# Adafruit_CAN_Bus_BFF.net
KiCad netlist of a schematic drawn in EAGLE
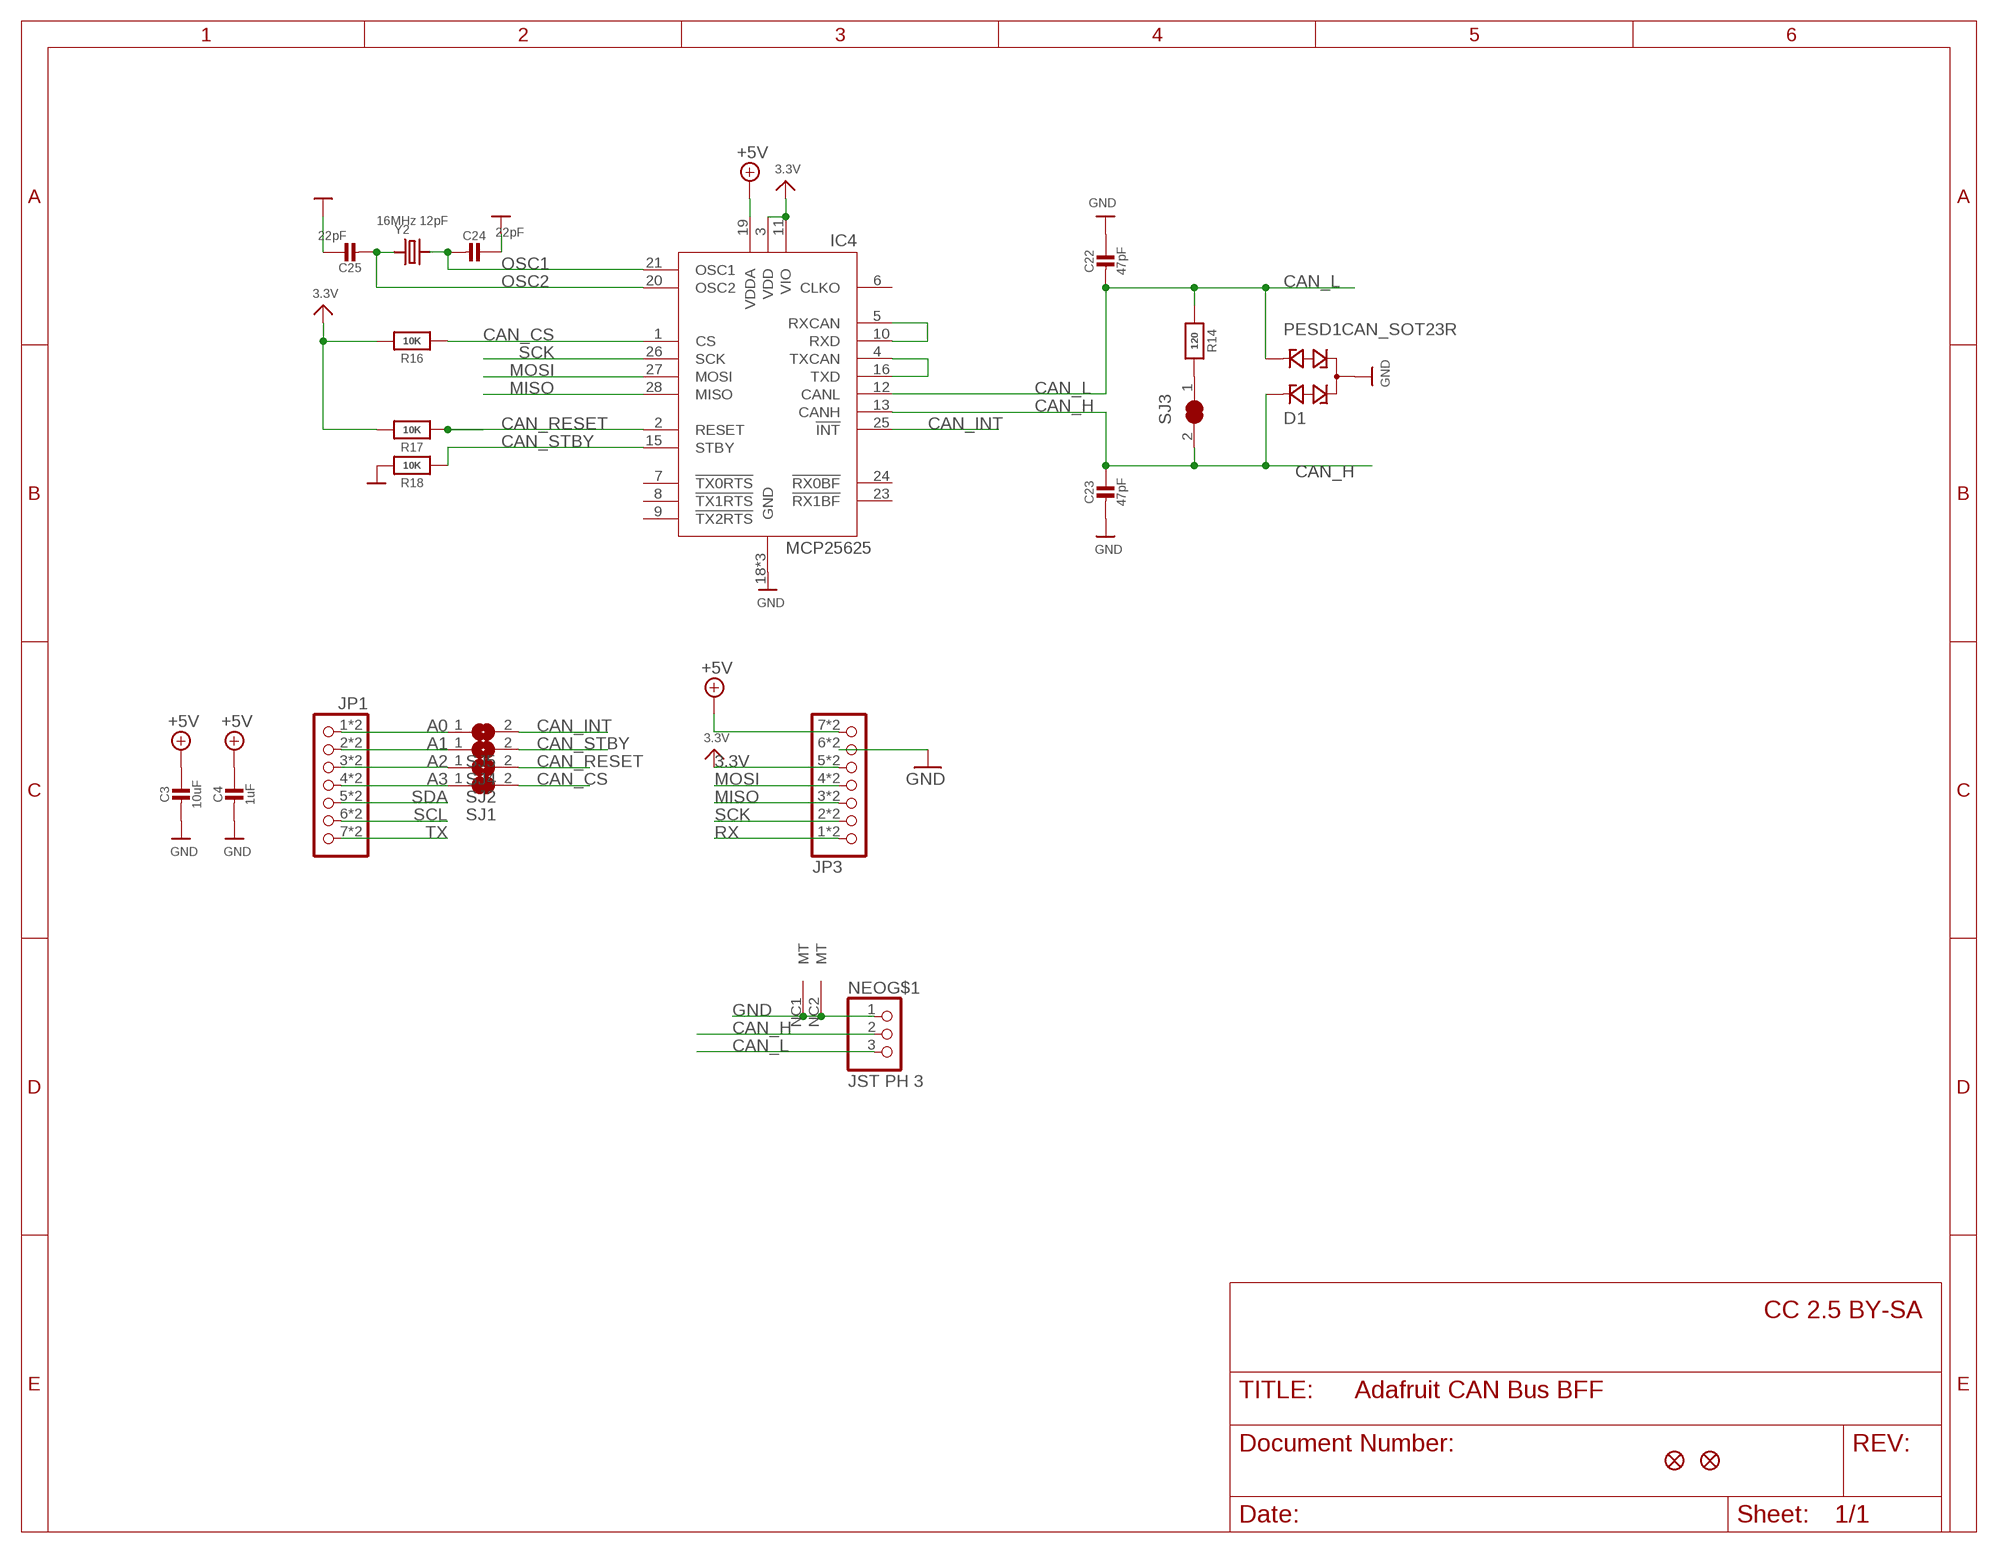
[diagram p0: schematic, sheet 1]

(export (version "E")
  (design (tool "Eeschema 10.0.6"))
  (components
    (comp (ref "C3")
      (value "10uF")
      (footprint "eagle-import:0805-NO")
      (libsource (lib "eagle-import") (part "CAP_CERAMIC0805-NOOUTLINE"))
    )
    (comp (ref "C4")
      (value "1uF")
      (footprint "eagle-import:0603-NO")
      (libsource (lib "eagle-import") (part "CAP_CERAMIC0603_NO"))
    )
    (comp (ref "C22")
      (value "47pF")
      (footprint "eagle-import:_0402NO")
      (libsource (lib "eagle-import") (part "CAP_CERAMIC_0402NO"))
    )
    (comp (ref "C23")
      (value "47pF")
      (footprint "eagle-import:_0402NO")
      (libsource (lib "eagle-import") (part "CAP_CERAMIC_0402NO"))
    )
    (comp (ref "C24")
      (value "22pF")
      (footprint "eagle-import:_0402NO")
      (libsource (lib "eagle-import") (part "CAP_CERAMIC_0402NO"))
    )
    (comp (ref "C25")
      (value "22pF")
      (footprint "eagle-import:_0402NO")
      (libsource (lib "eagle-import") (part "CAP_CERAMIC_0402NO"))
    )
    (comp (ref "D1")
      (value "PESD1CAN_SOT23R")
      (footprint "eagle-import:SOT23-R")
      (libsource (lib "eagle-import") (part "PESD1CAN_SOT23R"))
    )
    (comp (ref "IC4")
      (value "MCP25625")
      (footprint "eagle-import:QFN28-ML_6X6MM")
      (libsource (lib "eagle-import") (part "MCP25625"))
    )
    (comp (ref "JP1")
      (value "HEADER-1X7_CASTEL")
      (footprint "eagle-import:1X07_CASTEL")
      (libsource (lib "eagle-import") (part "HEADER-1X7_CASTEL"))
    )
    (comp (ref "JP3")
      (value "HEADER-1X7_CASTEL")
      (footprint "eagle-import:1X07_CASTEL")
      (libsource (lib "eagle-import") (part "HEADER-1X7_CASTEL"))
    )
    (comp (ref "NEO")
      (value "JST PH 3")
      (footprint "eagle-import:JSTPH3")
      (libsource (lib "eagle-import") (part "CON_JST_PH_3PIN"))
    )
    (comp (ref "R14")
      (value "120")
      (footprint "eagle-import:_0402NO")
      (libsource (lib "eagle-import") (part "RESISTOR_0402NO"))
    )
    (comp (ref "R16")
      (value "10K")
      (footprint "eagle-import:_0402NO")
      (libsource (lib "eagle-import") (part "RESISTOR_0402NO"))
    )
    (comp (ref "R17")
      (value "10K")
      (footprint "eagle-import:_0402NO")
      (libsource (lib "eagle-import") (part "RESISTOR_0402NO"))
    )
    (comp (ref "R18")
      (value "10K")
      (footprint "eagle-import:_0402NO")
      (libsource (lib "eagle-import") (part "RESISTOR_0402NO"))
    )
    (comp (ref "SJ1")
      (value "SOLDERJUMPER_CLOSED")
      (footprint "eagle-import:SOLDERJUMPER_CLOSEDWIRE")
      (libsource (lib "eagle-import") (part "SOLDERJUMPER_CLOSED"))
    )
    (comp (ref "SJ2")
      (value "SOLDERJUMPER")
      (footprint "eagle-import:SOLDERJUMPER_ARROW_NOPASTE")
      (libsource (lib "eagle-import") (part "SOLDERJUMPER"))
    )
    (comp (ref "SJ3")
      (value "SOLDERJUMPER_CLOSED")
      (footprint "eagle-import:SOLDERJUMPER_CLOSEDWIRE")
      (libsource (lib "eagle-import") (part "SOLDERJUMPER_CLOSED"))
    )
    (comp (ref "SJ4")
      (value "SOLDERJUMPER")
      (footprint "eagle-import:SOLDERJUMPER_ARROW_NOPASTE")
      (libsource (lib "eagle-import") (part "SOLDERJUMPER"))
    )
    (comp (ref "SJ5")
      (value "SOLDERJUMPER")
      (footprint "eagle-import:SOLDERJUMPER_ARROW_NOPASTE")
      (libsource (lib "eagle-import") (part "SOLDERJUMPER"))
    )
    (comp (ref "U$6")
      (value "FIDUCIAL_1MM")
      (footprint "eagle-import:FIDUCIAL_1MM")
      (libsource (lib "eagle-import") (part "FIDUCIAL_1MM"))
    )
    (comp (ref "U$8")
      (value "FIDUCIAL_1MM")
      (footprint "eagle-import:FIDUCIAL_1MM")
      (libsource (lib "eagle-import") (part "FIDUCIAL_1MM"))
    )
    (comp (ref "Y2")
      (value "16MHz 12pF")
      (footprint "eagle-import:CRYSTAL_2.5X2")
      (libsource (lib "eagle-import") (part "CRYSTAL2.5X2.0"))
    )
  )
  (nets
    (net (code "1") (name "+5V") (class "Default")
      (node (ref "C3") (pin "1") (pinfunction "1_1") (pintype "passive"))
      (node (ref "C4") (pin "1") (pinfunction "1_1") (pintype "passive"))
      (node (ref "IC4") (pin "19") (pinfunction "VDDA_19") (pintype "power_in"))
      (node (ref "JP3") (pin "7") (pinfunction "7_7") (pintype "passive"))
      (node (ref "JP3") (pin "7C") (pinfunction "7_7C") (pintype "passive"))
    )
    (net (code "2") (name "/A0") (class "Default")
      (node (ref "JP1") (pin "1") (pinfunction "1_1") (pintype "passive"))
      (node (ref "JP1") (pin "1C") (pinfunction "1_1C") (pintype "passive"))
      (node (ref "SJ5") (pin "1") (pinfunction "1_1") (pintype "passive"))
    )
    (net (code "3") (name "/A1") (class "Default")
      (node (ref "JP1") (pin "2") (pinfunction "2_2") (pintype "passive"))
      (node (ref "JP1") (pin "2C") (pinfunction "2_2C") (pintype "passive"))
      (node (ref "SJ4") (pin "1") (pinfunction "1_1") (pintype "passive"))
    )
    (net (code "4") (name "/A2") (class "Default")
      (node (ref "JP1") (pin "3") (pinfunction "3_3") (pintype "passive"))
      (node (ref "JP1") (pin "3C") (pinfunction "3_3C") (pintype "passive"))
      (node (ref "SJ2") (pin "1") (pinfunction "1_1") (pintype "passive"))
    )
    (net (code "5") (name "/A3") (class "Default")
      (node (ref "JP1") (pin "4") (pinfunction "4_4") (pintype "passive"))
      (node (ref "JP1") (pin "4C") (pinfunction "4_4C") (pintype "passive"))
      (node (ref "SJ1") (pin "1") (pinfunction "1_1") (pintype "passive"))
    )
    (net (code "6") (name "/CAN_CS") (class "Default")
      (node (ref "IC4") (pin "1") (pinfunction "CS_1") (pintype "input"))
      (node (ref "R16") (pin "1") (pinfunction "1_1") (pintype "passive"))
      (node (ref "SJ1") (pin "2") (pinfunction "2_2") (pintype "passive"))
    )
    (net (code "7") (name "/CAN_H") (class "Default")
      (node (ref "C23") (pin "1") (pinfunction "1_1") (pintype "passive"))
      (node (ref "D1") (pin "1") (pinfunction "1_1") (pintype "passive"))
      (node (ref "IC4") (pin "13") (pinfunction "CANH_13") (pintype "bidirectional"))
      (node (ref "NEO") (pin "2") (pinfunction "2_2") (pintype "passive"))
      (node (ref "SJ3") (pin "2") (pinfunction "2_2") (pintype "passive"))
    )
    (net (code "8") (name "/CAN_INT") (class "Default")
      (node (ref "IC4") (pin "25") (pinfunction "~{INT}_25") (pintype "output"))
      (node (ref "SJ5") (pin "2") (pinfunction "2_2") (pintype "passive"))
    )
    (net (code "9") (name "/CAN_L") (class "Default")
      (node (ref "C22") (pin "2") (pinfunction "2_2") (pintype "passive"))
      (node (ref "D1") (pin "2") (pinfunction "2_2") (pintype "passive"))
      (node (ref "IC4") (pin "12") (pinfunction "CANL_12") (pintype "bidirectional"))
      (node (ref "NEO") (pin "3") (pinfunction "3_3") (pintype "passive"))
      (node (ref "R14") (pin "1") (pinfunction "1_1") (pintype "passive"))
    )
    (net (code "10") (name "/CAN_RESET") (class "Default")
      (node (ref "IC4") (pin "2") (pinfunction "RESET_2") (pintype "input"))
      (node (ref "R17") (pin "1") (pinfunction "1_1") (pintype "passive"))
      (node (ref "SJ2") (pin "2") (pinfunction "2_2") (pintype "passive"))
    )
    (net (code "11") (name "/CAN_STBY") (class "Default")
      (node (ref "IC4") (pin "15") (pinfunction "STBY_15") (pintype "input"))
      (node (ref "R18") (pin "1") (pinfunction "1_1") (pintype "passive"))
      (node (ref "SJ4") (pin "2") (pinfunction "2_2") (pintype "passive"))
    )
    (net (code "12") (name "/MISO") (class "Default")
      (node (ref "IC4") (pin "28") (pinfunction "MISO_28") (pintype "output"))
      (node (ref "JP3") (pin "3") (pinfunction "3_3") (pintype "passive"))
      (node (ref "JP3") (pin "3C") (pinfunction "3_3C") (pintype "passive"))
    )
    (net (code "13") (name "/MOSI") (class "Default")
      (node (ref "IC4") (pin "27") (pinfunction "MOSI_27") (pintype "input"))
      (node (ref "JP3") (pin "4") (pinfunction "4_4") (pintype "passive"))
      (node (ref "JP3") (pin "4C") (pinfunction "4_4C") (pintype "passive"))
    )
    (net (code "14") (name "/OSC1") (class "Default")
      (node (ref "C24") (pin "2") (pinfunction "2_2") (pintype "passive"))
      (node (ref "IC4") (pin "21") (pinfunction "OSC1_21") (pintype "input"))
      (node (ref "Y2") (pin "3") (pinfunction "2_3") (pintype "passive"))
    )
    (net (code "15") (name "/OSC2") (class "Default")
      (node (ref "C25") (pin "2") (pinfunction "2_2") (pintype "passive"))
      (node (ref "IC4") (pin "20") (pinfunction "OSC2_20") (pintype "output"))
      (node (ref "Y2") (pin "1") (pinfunction "1_1") (pintype "passive"))
    )
    (net (code "16") (name "/RX") (class "Default")
      (node (ref "JP3") (pin "1") (pinfunction "1_1") (pintype "passive"))
      (node (ref "JP3") (pin "1C") (pinfunction "1_1C") (pintype "passive"))
    )
    (net (code "17") (name "/SCK") (class "Default")
      (node (ref "IC4") (pin "26") (pinfunction "SCK_26") (pintype "input"))
      (node (ref "JP3") (pin "2") (pinfunction "2_2") (pintype "passive"))
      (node (ref "JP3") (pin "2C") (pinfunction "2_2C") (pintype "passive"))
    )
    (net (code "18") (name "/SCL") (class "Default")
      (node (ref "JP1") (pin "6") (pinfunction "6_6") (pintype "passive"))
      (node (ref "JP1") (pin "6C") (pinfunction "6_6C") (pintype "passive"))
    )
    (net (code "19") (name "/SDA") (class "Default")
      (node (ref "JP1") (pin "5") (pinfunction "5_5") (pintype "passive"))
      (node (ref "JP1") (pin "5C") (pinfunction "5_5C") (pintype "passive"))
    )
    (net (code "20") (name "/TX") (class "Default")
      (node (ref "JP1") (pin "7") (pinfunction "7_7") (pintype "passive"))
      (node (ref "JP1") (pin "7C") (pinfunction "7_7C") (pintype "passive"))
    )
    (net (code "21") (name "3.3V") (class "Default")
      (node (ref "IC4") (pin "11") (pinfunction "VIO_11") (pintype "power_in"))
      (node (ref "IC4") (pin "3") (pinfunction "VDD_3") (pintype "power_in"))
      (node (ref "JP3") (pin "5") (pinfunction "5_5") (pintype "passive"))
      (node (ref "JP3") (pin "5C") (pinfunction "5_5C") (pintype "passive"))
      (node (ref "R16") (pin "2") (pinfunction "2_2") (pintype "passive"))
      (node (ref "R17") (pin "2") (pinfunction "2_2") (pintype "passive"))
    )
    (net (code "22") (name "GND") (class "Default")
      (node (ref "C22") (pin "1") (pinfunction "1_1") (pintype "passive"))
      (node (ref "C23") (pin "2") (pinfunction "2_2") (pintype "passive"))
      (node (ref "C24") (pin "1") (pinfunction "1_1") (pintype "passive"))
      (node (ref "C25") (pin "1") (pinfunction "1_1") (pintype "passive"))
      (node (ref "C3") (pin "2") (pinfunction "2_2") (pintype "passive"))
      (node (ref "C4") (pin "2") (pinfunction "2_2") (pintype "passive"))
      (node (ref "D1") (pin "3") (pinfunction "3_3") (pintype "passive"))
      (node (ref "IC4") (pin "18") (pinfunction "GND_18") (pintype "power_in"))
      (node (ref "IC4") (pin "22") (pinfunction "GND_22") (pintype "power_in"))
      (node (ref "IC4") (pin "EXP") (pinfunction "GND_EXP") (pintype "power_in"))
      (node (ref "JP3") (pin "6") (pinfunction "6_6") (pintype "passive"))
      (node (ref "JP3") (pin "6C") (pinfunction "6_6C") (pintype "passive"))
      (node (ref "NEO") (pin "1") (pinfunction "1_1") (pintype "passive"))
      (node (ref "NEO") (pin "NC1") (pinfunction "MT_NC1") (pintype "bidirectional"))
      (node (ref "NEO") (pin "NC2") (pinfunction "MT_NC2") (pintype "bidirectional"))
      (node (ref "R18") (pin "2") (pinfunction "2_2") (pintype "passive"))
    )
    (net (code "23") (name "Net-(IC4-RXCAN)") (class "Default")
      (node (ref "IC4") (pin "10") (pinfunction "RXD_10") (pintype "output"))
      (node (ref "IC4") (pin "5") (pinfunction "RXCAN_5") (pintype "input"))
    )
    (net (code "24") (name "Net-(IC4-TXCAN)") (class "Default")
      (node (ref "IC4") (pin "16") (pinfunction "TXD_16") (pintype "input"))
      (node (ref "IC4") (pin "4") (pinfunction "TXCAN_4") (pintype "output"))
    )
    (net (code "25") (name "Net-(R14-Pad2)") (class "Default")
      (node (ref "R14") (pin "2") (pinfunction "2_2") (pintype "passive"))
      (node (ref "SJ3") (pin "1") (pinfunction "1_1") (pintype "passive"))
    )
    (net (code "26") (name "unconnected-(IC4-CLKO-Pad6)") (class "Default")
      (node (ref "IC4") (pin "6") (pinfunction "CLKO_6") (pintype "output"))
    )
    (net (code "27") (name "unconnected-(IC4-~{RX0BF}-Pad24)") (class "Default")
      (node (ref "IC4") (pin "24") (pinfunction "~{RX0BF}_24") (pintype "output"))
    )
    (net (code "28") (name "unconnected-(IC4-~{RX1BF}-Pad23)") (class "Default")
      (node (ref "IC4") (pin "23") (pinfunction "~{RX1BF}_23") (pintype "output"))
    )
    (net (code "29") (name "unconnected-(IC4-~{TX0RTS}-Pad7)") (class "Default")
      (node (ref "IC4") (pin "7") (pinfunction "~{TX0RTS}_7") (pintype "input"))
    )
    (net (code "30") (name "unconnected-(IC4-~{TX1RTS}-Pad8)") (class "Default")
      (node (ref "IC4") (pin "8") (pinfunction "~{TX1RTS}_8") (pintype "input"))
    )
    (net (code "31") (name "unconnected-(IC4-~{TX2RTS}-Pad9)") (class "Default")
      (node (ref "IC4") (pin "9") (pinfunction "~{TX2RTS}_9") (pintype "input"))
    )
  )
)
